# shield_mega_seed4_mpu_lobo9.net
KiCad netlist of a schematic drawn in EAGLE
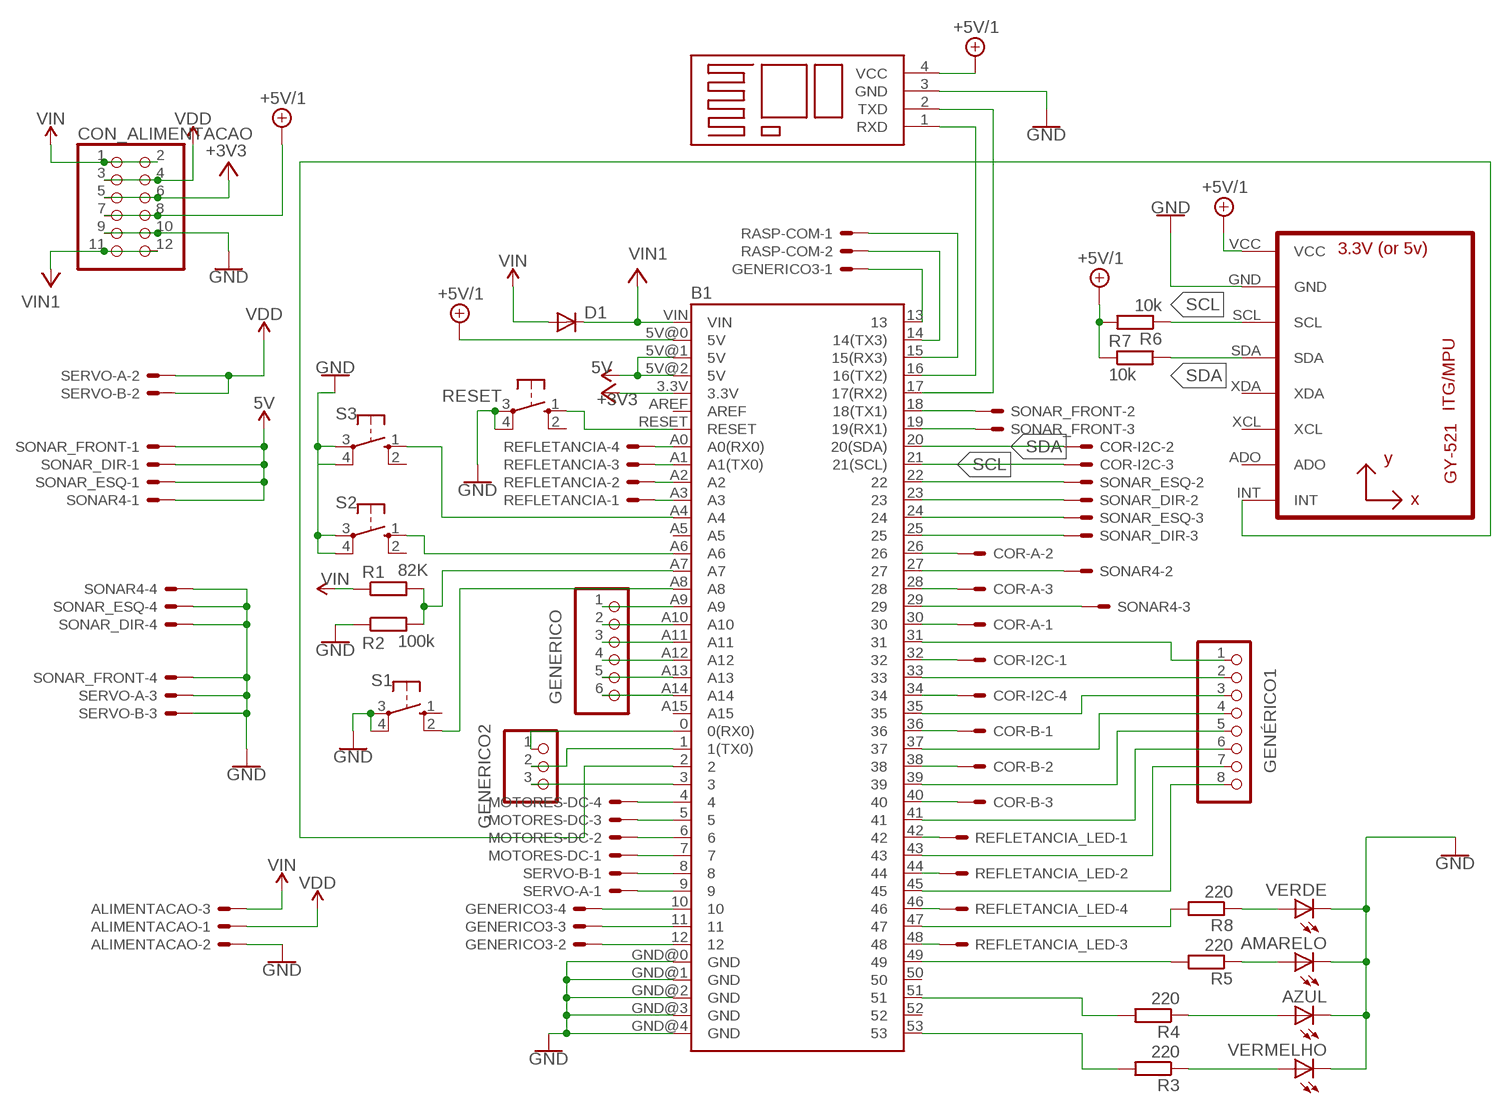
[diagram p0: schematic, sheet 1]

(export (version "E")
  (design (tool "Eeschema 10.0.6"))
  (components
    (comp (ref "ALIMENTACAO")
      (value "22-23-2031")
      (footprint "eagle-import:22-23-2031")
      (fields (field (name "MF") "MOLEX"))
      (libsource (lib "eagle-import") (part "22-23-2031"))
    )
    (comp (ref "AMARELO")
      (value "LED5MM")
      (footprint "eagle-import:LED5MM")
      (libsource (lib "eagle-import") (part "LED5MM"))
    )
    (comp (ref "AZUL")
      (value "LED5MM")
      (footprint "eagle-import:LED5MM")
      (libsource (lib "eagle-import") (part "LED5MM"))
    )
    (comp (ref "B1")
      (value "ARDUINO_MEGA_R3FULL")
      (footprint "eagle-import:ARDUINO_MEGA")
      (libsource (lib "eagle-import") (part "ARDUINO_MEGA_R3FULL"))
    )
    (comp (ref "B2")
      (value "BLUETOOTH")
      (footprint "eagle-import:BLUETOOTH")
      (libsource (lib "eagle-import") (part "BLUETOOTH"))
    )
    (comp (ref "CON_ALIMENTACAO")
      (value "PINHD-2X6")
      (footprint "eagle-import:2X06")
      (libsource (lib "eagle-import") (part "PINHD-2X6"))
    )
    (comp (ref "COR-A")
      (value "22-23-2031")
      (footprint "eagle-import:22-23-2031")
      (fields (field (name "MF") "MOLEX"))
      (libsource (lib "eagle-import") (part "22-23-2031"))
    )
    (comp (ref "COR-B")
      (value "22-23-2031")
      (footprint "eagle-import:22-23-2031")
      (fields (field (name "MF") "MOLEX"))
      (libsource (lib "eagle-import") (part "22-23-2031"))
    )
    (comp (ref "COR-I2C")
      (value "22-23-2041")
      (footprint "eagle-import:22-23-2041")
      (fields (field (name "MF") "MOLEX"))
      (libsource (lib "eagle-import") (part "22-23-2041"))
    )
    (comp (ref "D1")
      (value "1N4004")
      (footprint "eagle-import:DO41-10")
      (libsource (lib "eagle-import") (part "1N4004"))
    )
    (comp (ref "GENERICO")
      (value "PINHD-1X6")
      (footprint "eagle-import:1X06")
      (libsource (lib "eagle-import") (part "PINHD-1X6"))
    )
    (comp (ref "GENERICO2")
      (value "PINHD-1X3")
      (footprint "eagle-import:1X03")
      (libsource (lib "eagle-import") (part "PINHD-1X3"))
    )
    (comp (ref "GENERICO3")
      (value "22-23-2041")
      (footprint "eagle-import:22-23-2041")
      (fields (field (name "MF") "MOLEX"))
      (libsource (lib "eagle-import") (part "22-23-2041"))
    )
    (comp (ref "GENÉRICO1")
      (value "PINHD-1X8")
      (footprint "eagle-import:1X08")
      (libsource (lib "eagle-import") (part "PINHD-1X8"))
    )
    (comp (ref "MOTORES-DC")
      (value "22-23-2041")
      (footprint "eagle-import:22-23-2041")
      (fields (field (name "MF") "MOLEX"))
      (libsource (lib "eagle-import") (part "22-23-2041"))
    )
    (comp (ref "R1")
      (value "82K")
      (footprint "eagle-import:0204_7")
      (libsource (lib "eagle-import") (part "R-EU_0204/7"))
    )
    (comp (ref "R2")
      (value "100k")
      (footprint "eagle-import:0204_7")
      (libsource (lib "eagle-import") (part "R-EU_0204/7"))
    )
    (comp (ref "R3")
      (value "220")
      (footprint "eagle-import:0207_7")
      (libsource (lib "eagle-import") (part "R-EU_0207/7"))
    )
    (comp (ref "R4")
      (value "220")
      (footprint "eagle-import:0207_7")
      (libsource (lib "eagle-import") (part "R-EU_0207/7"))
    )
    (comp (ref "R5")
      (value "220")
      (footprint "eagle-import:0207_7")
      (libsource (lib "eagle-import") (part "R-EU_0207/7"))
    )
    (comp (ref "R6")
      (value "10k")
      (footprint "eagle-import:0204_7")
      (libsource (lib "eagle-import") (part "R-EU_0204/7"))
    )
    (comp (ref "R7")
      (value "10k")
      (footprint "eagle-import:0204_7")
      (libsource (lib "eagle-import") (part "R-EU_0204/7"))
    )
    (comp (ref "R8")
      (value "220")
      (footprint "eagle-import:0207_7")
      (libsource (lib "eagle-import") (part "R-EU_0207/7"))
    )
    (comp (ref "RASP-COM")
      (value "22-23-2021")
      (footprint "eagle-import:22-23-2021")
      (fields (field (name "MF") "MOLEX"))
      (libsource (lib "eagle-import") (part "22-23-2021"))
    )
    (comp (ref "REFLETANCIA")
      (value "22-23-2041")
      (footprint "eagle-import:22-23-2041")
      (fields (field (name "MF") "MOLEX"))
      (libsource (lib "eagle-import") (part "22-23-2041"))
    )
    (comp (ref "REFLETANCIA_LED")
      (value "22-23-2041")
      (footprint "eagle-import:22-23-2041")
      (fields (field (name "MF") "MOLEX"))
      (libsource (lib "eagle-import") (part "22-23-2041"))
    )
    (comp (ref "RESET")
      (value "10-XX")
      (footprint "eagle-import:B3F-10XX")
      (fields (field (name "MPN") "B3F-1000"))
      (libsource (lib "eagle-import") (part "10-XX"))
    )
    (comp (ref "S1")
      (value "10-XX")
      (footprint "eagle-import:B3F-10XX")
      (fields (field (name "MPN") "B3F-1000"))
      (libsource (lib "eagle-import") (part "10-XX"))
    )
    (comp (ref "S2")
      (value "10-XX")
      (footprint "eagle-import:B3F-10XX")
      (fields (field (name "MPN") "B3F-1000"))
      (libsource (lib "eagle-import") (part "10-XX"))
    )
    (comp (ref "S3")
      (value "10-XX")
      (footprint "eagle-import:B3F-10XX")
      (fields (field (name "MPN") "B3F-1000"))
      (libsource (lib "eagle-import") (part "10-XX"))
    )
    (comp (ref "SERVO-A")
      (value "22-23-2031")
      (footprint "eagle-import:22-23-2031")
      (fields (field (name "MF") "MOLEX"))
      (libsource (lib "eagle-import") (part "22-23-2031"))
    )
    (comp (ref "SERVO-B")
      (value "22-23-2031")
      (footprint "eagle-import:22-23-2031")
      (fields (field (name "MF") "MOLEX"))
      (libsource (lib "eagle-import") (part "22-23-2031"))
    )
    (comp (ref "SONAR4")
      (value "22-23-2041")
      (footprint "eagle-import:22-23-2041")
      (fields (field (name "MF") "MOLEX"))
      (libsource (lib "eagle-import") (part "22-23-2041"))
    )
    (comp (ref "SONAR_DIR")
      (value "22-23-2041")
      (footprint "eagle-import:22-23-2041")
      (fields (field (name "MF") "MOLEX"))
      (libsource (lib "eagle-import") (part "22-23-2041"))
    )
    (comp (ref "SONAR_ESQ")
      (value "22-23-2041")
      (footprint "eagle-import:22-23-2041")
      (fields (field (name "MF") "MOLEX"))
      (libsource (lib "eagle-import") (part "22-23-2041"))
    )
    (comp (ref "SONAR_FRONT")
      (value "22-23-2041")
      (footprint "eagle-import:22-23-2041")
      (fields (field (name "MF") "MOLEX"))
      (libsource (lib "eagle-import") (part "22-23-2041"))
    )
    (comp (ref "U1")
      (value "GY-521MPU6050")
      (footprint "eagle-import:GY-521")
      (libsource (lib "eagle-import") (part "GY-521MPU6050"))
    )
    (comp (ref "VERDE")
      (value "LED5MM")
      (footprint "eagle-import:LED5MM")
      (libsource (lib "eagle-import") (part "LED5MM"))
    )
    (comp (ref "VERMELHO")
      (value "LED5MM")
      (footprint "eagle-import:LED5MM")
      (libsource (lib "eagle-import") (part "LED5MM"))
    )
  )
  (nets
    (net (code "1") (name "+3V3") (class "Default")
      (node (ref "B1") (pin "3.3V") (pinfunction "3.3V_3.3V") (pintype "bidirectional"))
      (node (ref "CON_ALIMENTACAO") (pin "5") (pinfunction "5_5") (pintype "passive"))
      (node (ref "CON_ALIMENTACAO") (pin "6") (pinfunction "6_6") (pintype "passive"))
    )
    (net (code "2") (name "+5V{slash}1") (class "Default")
      (node (ref "B1") (pin "5V@0") (pinfunction "5V_5V@0") (pintype "bidirectional"))
      (node (ref "B2") (pin "4") (pinfunction "VCC_4") (pintype "power_in"))
      (node (ref "CON_ALIMENTACAO") (pin "7") (pinfunction "7_7") (pintype "passive"))
      (node (ref "CON_ALIMENTACAO") (pin "8") (pinfunction "8_8") (pintype "passive"))
      (node (ref "R6") (pin "2") (pinfunction "2_2") (pintype "passive"))
      (node (ref "R7") (pin "1") (pinfunction "1_1") (pintype "passive"))
      (node (ref "U1") (pin "VCC") (pinfunction "VCC_VCC") (pintype "bidirectional"))
    )
    (net (code "3") (name "5V") (class "Default")
      (node (ref "B1") (pin "5V@1") (pinfunction "5V_5V@1") (pintype "bidirectional"))
      (node (ref "B1") (pin "5V@2") (pinfunction "5V_5V@2") (pintype "bidirectional"))
      (node (ref "SONAR4") (pin "1") (pinfunction "S_1") (pintype "passive"))
      (node (ref "SONAR_DIR") (pin "1") (pinfunction "S_1") (pintype "passive"))
      (node (ref "SONAR_ESQ") (pin "1") (pinfunction "S_1") (pintype "passive"))
      (node (ref "SONAR_FRONT") (pin "1") (pinfunction "S_1") (pintype "passive"))
    )
    (net (code "4") (name "GND") (class "Default")
      (node (ref "ALIMENTACAO") (pin "2") (pinfunction "S_2") (pintype "passive"))
      (node (ref "AMARELO") (pin "K") (pinfunction "C_K") (pintype "passive"))
      (node (ref "AZUL") (pin "K") (pinfunction "C_K") (pintype "passive"))
      (node (ref "B1") (pin "GND@0") (pinfunction "GND_GND@0") (pintype "bidirectional"))
      (node (ref "B1") (pin "GND@1") (pinfunction "GND_GND@1") (pintype "bidirectional"))
      (node (ref "B1") (pin "GND@2") (pinfunction "GND_GND@2") (pintype "bidirectional"))
      (node (ref "B1") (pin "GND@3") (pinfunction "GND_GND@3") (pintype "bidirectional"))
      (node (ref "B1") (pin "GND@4") (pinfunction "GND_GND@4") (pintype "bidirectional"))
      (node (ref "B2") (pin "3") (pinfunction "GND_3") (pintype "power_in"))
      (node (ref "CON_ALIMENTACAO") (pin "10") (pinfunction "10_10") (pintype "passive"))
      (node (ref "CON_ALIMENTACAO") (pin "9") (pinfunction "9_9") (pintype "passive"))
      (node (ref "R2") (pin "1") (pinfunction "1_1") (pintype "passive"))
      (node (ref "RESET") (pin "3") (pinfunction "P_3") (pintype "passive"))
      (node (ref "RESET") (pin "4") (pinfunction "P1_4") (pintype "passive"))
      (node (ref "S1") (pin "3") (pinfunction "P_3") (pintype "passive"))
      (node (ref "S1") (pin "4") (pinfunction "P1_4") (pintype "passive"))
      (node (ref "S2") (pin "3") (pinfunction "P_3") (pintype "passive"))
      (node (ref "S2") (pin "4") (pinfunction "P1_4") (pintype "passive"))
      (node (ref "S3") (pin "3") (pinfunction "P_3") (pintype "passive"))
      (node (ref "S3") (pin "4") (pinfunction "P1_4") (pintype "passive"))
      (node (ref "SERVO-A") (pin "3") (pinfunction "S_3") (pintype "passive"))
      (node (ref "SERVO-B") (pin "3") (pinfunction "S_3") (pintype "passive"))
      (node (ref "SONAR4") (pin "4") (pinfunction "S_4") (pintype "passive"))
      (node (ref "SONAR_DIR") (pin "4") (pinfunction "S_4") (pintype "passive"))
      (node (ref "SONAR_ESQ") (pin "4") (pinfunction "S_4") (pintype "passive"))
      (node (ref "SONAR_FRONT") (pin "4") (pinfunction "S_4") (pintype "passive"))
      (node (ref "U1") (pin "GND") (pinfunction "GND_GND") (pintype "bidirectional"))
      (node (ref "VERDE") (pin "K") (pinfunction "C_K") (pintype "passive"))
      (node (ref "VERMELHO") (pin "K") (pinfunction "C_K") (pintype "passive"))
    )
    (net (code "5") (name "Net-(AMARELO-PadA)") (class "Default")
      (node (ref "AMARELO") (pin "A") (pinfunction "A_A") (pintype "passive"))
      (node (ref "R5") (pin "1") (pinfunction "1_1") (pintype "passive"))
    )
    (net (code "6") (name "Net-(AZUL-PadA)") (class "Default")
      (node (ref "AZUL") (pin "A") (pinfunction "A_A") (pintype "passive"))
      (node (ref "R4") (pin "1") (pinfunction "1_1") (pintype "passive"))
    )
    (net (code "7") (name "Net-(B1-0(RX0))") (class "Default")
      (node (ref "B1") (pin "0") (pinfunction "0(RX0)_0") (pintype "bidirectional"))
      (node (ref "GENERICO2") (pin "1") (pinfunction "1_1") (pintype "passive"))
    )
    (net (code "8") (name "Net-(B1-1(TX0))") (class "Default")
      (node (ref "B1") (pin "1") (pinfunction "1(TX0)_1") (pintype "bidirectional"))
      (node (ref "GENERICO2") (pin "2") (pinfunction "2_2") (pintype "passive"))
    )
    (net (code "9") (name "Net-(B1-14(TX3))") (class "Default")
      (node (ref "B1") (pin "14") (pinfunction "14(TX3)_14") (pintype "bidirectional"))
      (node (ref "RASP-COM") (pin "2") (pinfunction "S_2") (pintype "passive"))
    )
    (net (code "10") (name "Net-(B1-15(RX3))") (class "Default")
      (node (ref "B1") (pin "15") (pinfunction "15(RX3)_15") (pintype "bidirectional"))
      (node (ref "RASP-COM") (pin "1") (pinfunction "S_1") (pintype "passive"))
    )
    (net (code "11") (name "Net-(B1-16(TX2))") (class "Default")
      (node (ref "B1") (pin "16") (pinfunction "16(TX2)_16") (pintype "bidirectional"))
      (node (ref "B2") (pin "1") (pinfunction "RXD_1") (pintype "bidirectional"))
    )
    (net (code "12") (name "Net-(B1-17(RX2))") (class "Default")
      (node (ref "B1") (pin "17") (pinfunction "17(RX2)_17") (pintype "bidirectional"))
      (node (ref "B2") (pin "2") (pinfunction "TXD_2") (pintype "bidirectional"))
    )
    (net (code "13") (name "Net-(B1-18(TX1))") (class "Default")
      (node (ref "B1") (pin "18") (pinfunction "18(TX1)_18") (pintype "bidirectional"))
      (node (ref "SONAR_FRONT") (pin "2") (pinfunction "S_2") (pintype "passive"))
    )
    (net (code "14") (name "Net-(B1-19(RX1))") (class "Default")
      (node (ref "B1") (pin "19") (pinfunction "19(RX1)_19") (pintype "bidirectional"))
      (node (ref "SONAR_FRONT") (pin "3") (pinfunction "S_3") (pintype "passive"))
    )
    (net (code "15") (name "Net-(B1-A0(RX0))") (class "Default")
      (node (ref "B1") (pin "A0") (pinfunction "A0(RX0)_A0") (pintype "bidirectional"))
      (node (ref "REFLETANCIA") (pin "4") (pinfunction "S_4") (pintype "passive"))
    )
    (net (code "16") (name "Net-(B1-A1(TX0))") (class "Default")
      (node (ref "B1") (pin "A1") (pinfunction "A1(TX0)_A1") (pintype "bidirectional"))
      (node (ref "REFLETANCIA") (pin "3") (pinfunction "S_3") (pintype "passive"))
    )
    (net (code "17") (name "Net-(B1-Pad2)") (class "Default")
      (node (ref "B1") (pin "2") (pinfunction "2_2") (pintype "bidirectional"))
      (node (ref "U1") (pin "INT") (pinfunction "INT_INT") (pintype "bidirectional"))
    )
    (net (code "18") (name "Net-(B1-Pad3)") (class "Default")
      (node (ref "B1") (pin "3") (pinfunction "3_3") (pintype "bidirectional"))
      (node (ref "GENERICO2") (pin "3") (pinfunction "3_3") (pintype "passive"))
    )
    (net (code "19") (name "Net-(B1-Pad31)") (class "Default")
      (node (ref "B1") (pin "31") (pinfunction "31_31") (pintype "bidirectional"))
      (node (ref "GENÉRICO1") (pin "1") (pinfunction "1_1") (pintype "passive"))
    )
    (net (code "20") (name "Net-(B1-Pad33)") (class "Default")
      (node (ref "B1") (pin "33") (pinfunction "33_33") (pintype "bidirectional"))
      (node (ref "GENÉRICO1") (pin "2") (pinfunction "2_2") (pintype "passive"))
    )
    (net (code "21") (name "Net-(B1-Pad35)") (class "Default")
      (node (ref "B1") (pin "35") (pinfunction "35_35") (pintype "bidirectional"))
      (node (ref "GENÉRICO1") (pin "3") (pinfunction "3_3") (pintype "passive"))
    )
    (net (code "22") (name "Net-(B1-Pad37)") (class "Default")
      (node (ref "B1") (pin "37") (pinfunction "37_37") (pintype "bidirectional"))
      (node (ref "GENÉRICO1") (pin "4") (pinfunction "4_4") (pintype "passive"))
    )
    (net (code "23") (name "Net-(B1-Pad39)") (class "Default")
      (node (ref "B1") (pin "39") (pinfunction "39_39") (pintype "bidirectional"))
      (node (ref "GENÉRICO1") (pin "5") (pinfunction "5_5") (pintype "passive"))
    )
    (net (code "24") (name "Net-(B1-Pad41)") (class "Default")
      (node (ref "B1") (pin "41") (pinfunction "41_41") (pintype "bidirectional"))
      (node (ref "GENÉRICO1") (pin "6") (pinfunction "6_6") (pintype "passive"))
    )
    (net (code "25") (name "Net-(B1-Pad43)") (class "Default")
      (node (ref "B1") (pin "43") (pinfunction "43_43") (pintype "bidirectional"))
      (node (ref "GENÉRICO1") (pin "7") (pinfunction "7_7") (pintype "passive"))
    )
    (net (code "26") (name "Net-(B1-Pad45)") (class "Default")
      (node (ref "B1") (pin "45") (pinfunction "45_45") (pintype "bidirectional"))
      (node (ref "GENÉRICO1") (pin "8") (pinfunction "8_8") (pintype "passive"))
    )
    (net (code "27") (name "Net-(B1-Pad47)") (class "Default")
      (node (ref "B1") (pin "47") (pinfunction "47_47") (pintype "bidirectional"))
      (node (ref "R8") (pin "2") (pinfunction "2_2") (pintype "passive"))
    )
    (net (code "28") (name "Net-(B1-Pad49)") (class "Default")
      (node (ref "B1") (pin "49") (pinfunction "49_49") (pintype "bidirectional"))
      (node (ref "R5") (pin "2") (pinfunction "2_2") (pintype "passive"))
    )
    (net (code "29") (name "Net-(B1-Pad51)") (class "Default")
      (node (ref "B1") (pin "51") (pinfunction "51_51") (pintype "bidirectional"))
      (node (ref "R4") (pin "2") (pinfunction "2_2") (pintype "passive"))
    )
    (net (code "30") (name "Net-(B1-Pad53)") (class "Default")
      (node (ref "B1") (pin "53") (pinfunction "53_53") (pintype "bidirectional"))
      (node (ref "R3") (pin "2") (pinfunction "2_2") (pintype "passive"))
    )
    (net (code "31") (name "Net-(B1-PadA7)") (class "Default")
      (node (ref "B1") (pin "A7") (pinfunction "A7_A7") (pintype "bidirectional"))
      (node (ref "R1") (pin "2") (pinfunction "2_2") (pintype "passive"))
      (node (ref "R2") (pin "2") (pinfunction "2_2") (pintype "passive"))
    )
    (net (code "32") (name "Net-(B1-PadA9)") (class "Default")
      (node (ref "B1") (pin "A9") (pinfunction "A9_A9") (pintype "bidirectional"))
      (node (ref "GENERICO") (pin "1") (pinfunction "1_1") (pintype "passive"))
    )
    (net (code "33") (name "Net-(B1-PadA10)") (class "Default")
      (node (ref "B1") (pin "A10") (pinfunction "A10_A10") (pintype "bidirectional"))
      (node (ref "GENERICO") (pin "2") (pinfunction "2_2") (pintype "passive"))
    )
    (net (code "34") (name "Net-(B1-PadA11)") (class "Default")
      (node (ref "B1") (pin "A11") (pinfunction "A11_A11") (pintype "bidirectional"))
      (node (ref "GENERICO") (pin "3") (pinfunction "3_3") (pintype "passive"))
    )
    (net (code "35") (name "Net-(B1-PadA12)") (class "Default")
      (node (ref "B1") (pin "A12") (pinfunction "A12_A12") (pintype "bidirectional"))
      (node (ref "GENERICO") (pin "4") (pinfunction "4_4") (pintype "passive"))
    )
    (net (code "36") (name "Net-(B1-PadA13)") (class "Default")
      (node (ref "B1") (pin "A13") (pinfunction "A13_A13") (pintype "bidirectional"))
      (node (ref "GENERICO") (pin "5") (pinfunction "5_5") (pintype "passive"))
    )
    (net (code "37") (name "Net-(B1-PadA14)") (class "Default")
      (node (ref "B1") (pin "A14") (pinfunction "A14_A14") (pintype "bidirectional"))
      (node (ref "GENERICO") (pin "6") (pinfunction "6_6") (pintype "passive"))
    )
    (net (code "38") (name "Net-(COR-AA-S)") (class "Default")
      (node (ref "B1") (pin "30") (pinfunction "30_30") (pintype "bidirectional"))
      (node (ref "COR-A") (pin "1") (pinfunction "S_1") (pintype "passive"))
    )
    (net (code "39") (name "Net-(COR-AB-S)") (class "Default")
      (node (ref "B1") (pin "26") (pinfunction "26_26") (pintype "bidirectional"))
      (node (ref "COR-A") (pin "2") (pinfunction "S_2") (pintype "passive"))
    )
    (net (code "40") (name "Net-(COR-AC-S)") (class "Default")
      (node (ref "B1") (pin "28") (pinfunction "28_28") (pintype "bidirectional"))
      (node (ref "COR-A") (pin "3") (pinfunction "S_3") (pintype "passive"))
    )
    (net (code "41") (name "Net-(COR-BA-S)") (class "Default")
      (node (ref "B1") (pin "36") (pinfunction "36_36") (pintype "bidirectional"))
      (node (ref "COR-B") (pin "1") (pinfunction "S_1") (pintype "passive"))
    )
    (net (code "42") (name "Net-(COR-BB-S)") (class "Default")
      (node (ref "B1") (pin "38") (pinfunction "38_38") (pintype "bidirectional"))
      (node (ref "COR-B") (pin "2") (pinfunction "S_2") (pintype "passive"))
    )
    (net (code "43") (name "Net-(COR-BC-S)") (class "Default")
      (node (ref "B1") (pin "40") (pinfunction "40_40") (pintype "bidirectional"))
      (node (ref "COR-B") (pin "3") (pinfunction "S_3") (pintype "passive"))
    )
    (net (code "44") (name "Net-(COR-I2CA-S)") (class "Default")
      (node (ref "B1") (pin "32") (pinfunction "32_32") (pintype "bidirectional"))
      (node (ref "COR-I2C") (pin "1") (pinfunction "S_1") (pintype "passive"))
    )
    (net (code "45") (name "Net-(COR-I2CD-S)") (class "Default")
      (node (ref "B1") (pin "34") (pinfunction "34_34") (pintype "bidirectional"))
      (node (ref "COR-I2C") (pin "4") (pinfunction "S_4") (pintype "passive"))
    )
    (net (code "46") (name "Net-(GENERICO3A-S)") (class "Default")
      (node (ref "B1") (pin "13") (pinfunction "13_13") (pintype "bidirectional"))
      (node (ref "GENERICO3") (pin "1") (pinfunction "S_1") (pintype "passive"))
    )
    (net (code "47") (name "Net-(GENERICO3B-S)") (class "Default")
      (node (ref "B1") (pin "12") (pinfunction "12_12") (pintype "bidirectional"))
      (node (ref "GENERICO3") (pin "2") (pinfunction "S_2") (pintype "passive"))
    )
    (net (code "48") (name "Net-(GENERICO3C-S)") (class "Default")
      (node (ref "B1") (pin "11") (pinfunction "11_11") (pintype "bidirectional"))
      (node (ref "GENERICO3") (pin "3") (pinfunction "S_3") (pintype "passive"))
    )
    (net (code "49") (name "Net-(GENERICO3D-S)") (class "Default")
      (node (ref "B1") (pin "10") (pinfunction "10_10") (pintype "bidirectional"))
      (node (ref "GENERICO3") (pin "4") (pinfunction "S_4") (pintype "passive"))
    )
    (net (code "50") (name "Net-(MOTORES-DCA-S)") (class "Default")
      (node (ref "B1") (pin "7") (pinfunction "7_7") (pintype "bidirectional"))
      (node (ref "MOTORES-DC") (pin "1") (pinfunction "S_1") (pintype "passive"))
    )
    (net (code "51") (name "Net-(MOTORES-DCB-S)") (class "Default")
      (node (ref "B1") (pin "6") (pinfunction "6_6") (pintype "bidirectional"))
      (node (ref "MOTORES-DC") (pin "2") (pinfunction "S_2") (pintype "passive"))
    )
    (net (code "52") (name "Net-(MOTORES-DCC-S)") (class "Default")
      (node (ref "B1") (pin "5") (pinfunction "5_5") (pintype "bidirectional"))
      (node (ref "MOTORES-DC") (pin "3") (pinfunction "S_3") (pintype "passive"))
    )
    (net (code "53") (name "Net-(MOTORES-DCD-S)") (class "Default")
      (node (ref "B1") (pin "4") (pinfunction "4_4") (pintype "bidirectional"))
      (node (ref "MOTORES-DC") (pin "4") (pinfunction "S_4") (pintype "passive"))
    )
    (net (code "54") (name "Net-(R3-Pad1)") (class "Default")
      (node (ref "R3") (pin "1") (pinfunction "1_1") (pintype "passive"))
      (node (ref "VERMELHO") (pin "A") (pinfunction "A_A") (pintype "passive"))
    )
    (net (code "55") (name "Net-(R8-Pad1)") (class "Default")
      (node (ref "R8") (pin "1") (pinfunction "1_1") (pintype "passive"))
      (node (ref "VERDE") (pin "A") (pinfunction "A_A") (pintype "passive"))
    )
    (net (code "56") (name "Net-(REFLETANCIAA-S)") (class "Default")
      (node (ref "B1") (pin "A3") (pinfunction "A3_A3") (pintype "bidirectional"))
      (node (ref "REFLETANCIA") (pin "1") (pinfunction "S_1") (pintype "passive"))
    )
    (net (code "57") (name "Net-(REFLETANCIAB-S)") (class "Default")
      (node (ref "B1") (pin "A2") (pinfunction "A2_A2") (pintype "bidirectional"))
      (node (ref "REFLETANCIA") (pin "2") (pinfunction "S_2") (pintype "passive"))
    )
    (net (code "58") (name "Net-(REFLETANCIA_LEDA-S)") (class "Default")
      (node (ref "B1") (pin "42") (pinfunction "42_42") (pintype "bidirectional"))
      (node (ref "REFLETANCIA_LED") (pin "1") (pinfunction "S_1") (pintype "passive"))
    )
    (net (code "59") (name "Net-(REFLETANCIA_LEDB-S)") (class "Default")
      (node (ref "B1") (pin "44") (pinfunction "44_44") (pintype "bidirectional"))
      (node (ref "REFLETANCIA_LED") (pin "2") (pinfunction "S_2") (pintype "passive"))
    )
    (net (code "60") (name "Net-(REFLETANCIA_LEDC-S)") (class "Default")
      (node (ref "B1") (pin "48") (pinfunction "48_48") (pintype "bidirectional"))
      (node (ref "REFLETANCIA_LED") (pin "3") (pinfunction "S_3") (pintype "passive"))
    )
    (net (code "61") (name "Net-(REFLETANCIA_LEDD-S)") (class "Default")
      (node (ref "B1") (pin "46") (pinfunction "46_46") (pintype "bidirectional"))
      (node (ref "REFLETANCIA_LED") (pin "4") (pinfunction "S_4") (pintype "passive"))
    )
    (net (code "62") (name "Net-(RESET-S)") (class "Default")
      (node (ref "B1") (pin "RESET") (pinfunction "RESET_RESET") (pintype "bidirectional"))
      (node (ref "RESET") (pin "1") (pinfunction "S_1") (pintype "passive"))
    )
    (net (code "63") (name "Net-(S1-S1)") (class "Default")
      (node (ref "B1") (pin "A8") (pinfunction "A8_A8") (pintype "bidirectional"))
      (node (ref "S1") (pin "2") (pinfunction "S1_2") (pintype "passive"))
    )
    (net (code "64") (name "Net-(S2-S)") (class "Default")
      (node (ref "B1") (pin "A6") (pinfunction "A6_A6") (pintype "bidirectional"))
      (node (ref "S2") (pin "1") (pinfunction "S_1") (pintype "passive"))
    )
    (net (code "65") (name "Net-(S3-S)") (class "Default")
      (node (ref "B1") (pin "A4") (pinfunction "A4_A4") (pintype "bidirectional"))
      (node (ref "S3") (pin "1") (pinfunction "S_1") (pintype "passive"))
    )
    (net (code "66") (name "Net-(SERVO-AA-S)") (class "Default")
      (node (ref "B1") (pin "9") (pinfunction "9_9") (pintype "bidirectional"))
      (node (ref "SERVO-A") (pin "1") (pinfunction "S_1") (pintype "passive"))
    )
    (net (code "67") (name "Net-(SERVO-BA-S)") (class "Default")
      (node (ref "B1") (pin "8") (pinfunction "8_8") (pintype "bidirectional"))
      (node (ref "SERVO-B") (pin "1") (pinfunction "S_1") (pintype "passive"))
    )
    (net (code "68") (name "Net-(SONAR4B-S)") (class "Default")
      (node (ref "B1") (pin "27") (pinfunction "27_27") (pintype "bidirectional"))
      (node (ref "SONAR4") (pin "2") (pinfunction "S_2") (pintype "passive"))
    )
    (net (code "69") (name "Net-(SONAR4C-S)") (class "Default")
      (node (ref "B1") (pin "29") (pinfunction "29_29") (pintype "bidirectional"))
      (node (ref "SONAR4") (pin "3") (pinfunction "S_3") (pintype "passive"))
    )
    (net (code "70") (name "Net-(SONAR_DIRB-S)") (class "Default")
      (node (ref "B1") (pin "23") (pinfunction "23_23") (pintype "bidirectional"))
      (node (ref "SONAR_DIR") (pin "2") (pinfunction "S_2") (pintype "passive"))
    )
    (net (code "71") (name "Net-(SONAR_DIRC-S)") (class "Default")
      (node (ref "B1") (pin "25") (pinfunction "25_25") (pintype "bidirectional"))
      (node (ref "SONAR_DIR") (pin "3") (pinfunction "S_3") (pintype "passive"))
    )
    (net (code "72") (name "Net-(SONAR_ESQB-S)") (class "Default")
      (node (ref "B1") (pin "22") (pinfunction "22_22") (pintype "bidirectional"))
      (node (ref "SONAR_ESQ") (pin "2") (pinfunction "S_2") (pintype "passive"))
    )
    (net (code "73") (name "Net-(SONAR_ESQC-S)") (class "Default")
      (node (ref "B1") (pin "24") (pinfunction "24_24") (pintype "bidirectional"))
      (node (ref "SONAR_ESQ") (pin "3") (pinfunction "S_3") (pintype "passive"))
    )
    (net (code "74") (name "SCL") (class "Default")
      (node (ref "B1") (pin "21") (pinfunction "21(SCL)_21") (pintype "bidirectional"))
      (node (ref "COR-I2C") (pin "3") (pinfunction "S_3") (pintype "passive"))
      (node (ref "R6") (pin "1") (pinfunction "1_1") (pintype "passive"))
      (node (ref "U1") (pin "SCL") (pinfunction "SCL_SCL") (pintype "bidirectional"))
    )
    (net (code "75") (name "SDA") (class "Default")
      (node (ref "B1") (pin "20") (pinfunction "20(SDA)_20") (pintype "bidirectional"))
      (node (ref "COR-I2C") (pin "2") (pinfunction "S_2") (pintype "passive"))
      (node (ref "R7") (pin "2") (pinfunction "2_2") (pintype "passive"))
      (node (ref "U1") (pin "SDA") (pinfunction "SDA_SDA") (pintype "bidirectional"))
    )
    (net (code "76") (name "VDD") (class "Default")
      (node (ref "ALIMENTACAO") (pin "1") (pinfunction "S_1") (pintype "passive"))
      (node (ref "CON_ALIMENTACAO") (pin "3") (pinfunction "3_3") (pintype "passive"))
      (node (ref "CON_ALIMENTACAO") (pin "4") (pinfunction "4_4") (pintype "passive"))
      (node (ref "SERVO-A") (pin "2") (pinfunction "S_2") (pintype "passive"))
      (node (ref "SERVO-B") (pin "2") (pinfunction "S_2") (pintype "passive"))
    )
    (net (code "77") (name "VIN") (class "Default")
      (node (ref "ALIMENTACAO") (pin "3") (pinfunction "S_3") (pintype "passive"))
      (node (ref "CON_ALIMENTACAO") (pin "1") (pinfunction "1_1") (pintype "passive"))
      (node (ref "CON_ALIMENTACAO") (pin "2") (pinfunction "2_2") (pintype "passive"))
      (node (ref "D1") (pin "A") (pinfunction "A_A") (pintype "passive"))
      (node (ref "R1") (pin "1") (pinfunction "1_1") (pintype "passive"))
    )
    (net (code "78") (name "VIN1") (class "Default")
      (node (ref "B1") (pin "VIN") (pinfunction "VIN_VIN") (pintype "bidirectional"))
      (node (ref "CON_ALIMENTACAO") (pin "11") (pinfunction "11_11") (pintype "passive"))
      (node (ref "CON_ALIMENTACAO") (pin "12") (pinfunction "12_12") (pintype "passive"))
      (node (ref "D1") (pin "C") (pinfunction "C_C") (pintype "passive"))
    )
    (net (code "79") (name "unconnected-(B1-Pad50)") (class "Default")
      (node (ref "B1") (pin "50") (pinfunction "50_50") (pintype "bidirectional"))
    )
    (net (code "80") (name "unconnected-(B1-Pad52)") (class "Default")
      (node (ref "B1") (pin "52") (pinfunction "52_52") (pintype "bidirectional"))
    )
    (net (code "81") (name "unconnected-(B1-PadA5)") (class "Default")
      (node (ref "B1") (pin "A5") (pinfunction "A5_A5") (pintype "bidirectional"))
    )
    (net (code "82") (name "unconnected-(B1-PadA15)") (class "Default")
      (node (ref "B1") (pin "A15") (pinfunction "A15_A15") (pintype "bidirectional"))
    )
    (net (code "83") (name "unconnected-(B1-PadAREF)") (class "Default")
      (node (ref "B1") (pin "AREF") (pinfunction "AREF_AREF") (pintype "bidirectional"))
    )
    (net (code "84") (name "unconnected-(RESET-S1-Pad2)") (class "Default")
      (node (ref "RESET") (pin "2") (pinfunction "S1_2") (pintype "passive"))
    )
    (net (code "85") (name "unconnected-(S1-S-Pad1)") (class "Default")
      (node (ref "S1") (pin "1") (pinfunction "S_1") (pintype "passive"))
    )
    (net (code "86") (name "unconnected-(S2-S1-Pad2)") (class "Default")
      (node (ref "S2") (pin "2") (pinfunction "S1_2") (pintype "passive"))
    )
    (net (code "87") (name "unconnected-(S3-S1-Pad2)") (class "Default")
      (node (ref "S3") (pin "2") (pinfunction "S1_2") (pintype "passive"))
    )
    (net (code "88") (name "unconnected-(U1-PadADO)") (class "Default")
      (node (ref "U1") (pin "ADO") (pinfunction "ADO_ADO") (pintype "bidirectional"))
    )
    (net (code "89") (name "unconnected-(U1-PadXCL)") (class "Default")
      (node (ref "U1") (pin "XCL") (pinfunction "XCL_XCL") (pintype "bidirectional"))
    )
    (net (code "90") (name "unconnected-(U1-PadXDA)") (class "Default")
      (node (ref "U1") (pin "XDA") (pinfunction "XDA_XDA") (pintype "bidirectional"))
    )
  )
)
